# NeoJointV2A-090.net
KiCad netlist of a schematic drawn in EAGLE
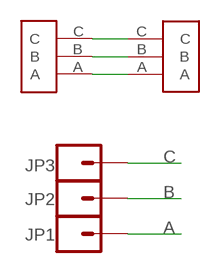
[diagram p0: schematic, sheet 1]

(export (version "E")
  (design (tool "Eeschema 10.0.6"))
  (components
    (comp (ref "JP1")
      (value "M01PTH")
      (footprint "eagle-import:1X01")
      (libsource (lib "eagle-import") (part "M01PTH"))
    )
    (comp (ref "JP2")
      (value "M01PTH")
      (footprint "eagle-import:1X01")
      (libsource (lib "eagle-import") (part "M01PTH"))
    )
    (comp (ref "JP3")
      (value "M01PTH")
      (footprint "eagle-import:1X01")
      (libsource (lib "eagle-import") (part "M01PTH"))
    )
    (comp (ref "U$1")
      (value "LED_STRIP_3P")
      (footprint "eagle-import:LEDSTRIP-3P")
      (libsource (lib "eagle-import") (part "LED_STRIP_3P"))
    )
    (comp (ref "U$2")
      (value "LED_STRIP_3P")
      (footprint "eagle-import:LEDSTRIP-3P")
      (libsource (lib "eagle-import") (part "LED_STRIP_3P"))
    )
  )
  (nets
    (net (code "1") (name "/A") (class "Default")
      (node (ref "JP1") (pin "1") (pinfunction "1_1") (pintype "passive"))
      (node (ref "U$1") (pin "A") (pinfunction "A_A") (pintype "bidirectional"))
      (node (ref "U$2") (pin "A") (pinfunction "A_A") (pintype "bidirectional"))
    )
    (net (code "2") (name "/B") (class "Default")
      (node (ref "JP2") (pin "1") (pinfunction "1_1") (pintype "passive"))
      (node (ref "U$1") (pin "B") (pinfunction "B_B") (pintype "bidirectional"))
      (node (ref "U$2") (pin "B") (pinfunction "B_B") (pintype "bidirectional"))
    )
    (net (code "3") (name "/C") (class "Default")
      (node (ref "JP3") (pin "1") (pinfunction "1_1") (pintype "passive"))
      (node (ref "U$1") (pin "C") (pinfunction "C_C") (pintype "bidirectional"))
      (node (ref "U$2") (pin "C") (pinfunction "C_C") (pintype "bidirectional"))
    )
  )
)
